# ENCODER.net
KiCad netlist of a schematic drawn in Altium Designer
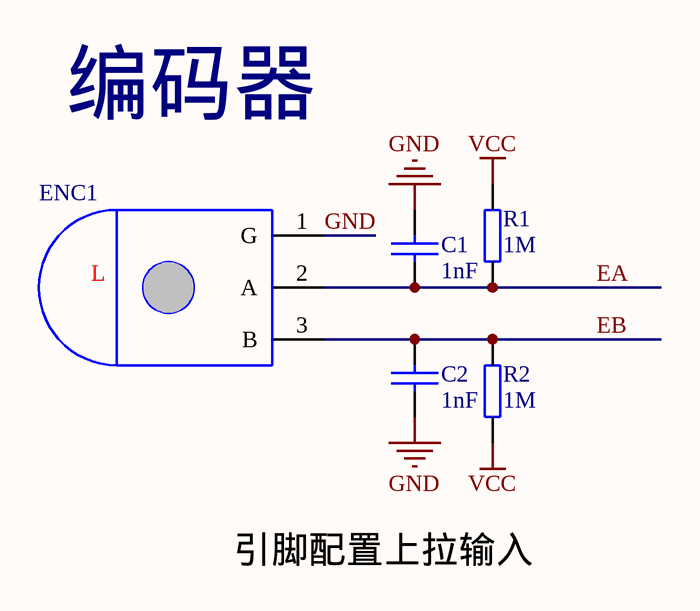
[diagram p0: ENCODER.SchDoc]

(export (version "E")
  (design (tool "Eeschema 10.0.6"))
  (components
    (comp (ref "C1")
      (value "1nF")
      (footprint "0402_C")
      (description "Capacitor")
      (libsource (lib "wch_sch_others(1)") (part "CAP"))
    )
    (comp (ref "C2")
      (value "1nF")
      (footprint "0402_C")
      (description "Capacitor")
      (libsource (lib "wch_sch_others(1)") (part "CAP"))
    )
    (comp (ref "ENC1") (value "~") (footprint "ENC-11-2") (libsource (lib "*") (part "ENC")))
    (comp (ref "R1") (value "1M") (footprint "0402") (libsource (lib "wch_sch_others") (part "RES")))
    (comp (ref "R2") (value "1M") (footprint "0402") (libsource (lib "wch_sch_others") (part "RES")))
  )
  (nets
    (net (code "1") (name "/EA") (class "Default")
      (node (ref "C1") (pin "2") (pinfunction "2_2") (pintype "passive"))
      (node (ref "ENC1") (pin "2") (pinfunction "A_2") (pintype "passive"))
      (node (ref "R1") (pin "2") (pintype "passive"))
    )
    (net (code "2") (name "/EB") (class "Default")
      (node (ref "C2") (pin "2") (pinfunction "2_2") (pintype "passive"))
      (node (ref "ENC1") (pin "3") (pinfunction "B_3") (pintype "passive"))
      (node (ref "R2") (pin "1") (pintype "passive"))
    )
    (net (code "3") (name "GND") (class "Default")
      (node (ref "C1") (pin "1") (pinfunction "1_1") (pintype "passive"))
      (node (ref "C2") (pin "1") (pinfunction "1_1") (pintype "passive"))
      (node (ref "ENC1") (pin "1") (pinfunction "G_1") (pintype "passive"))
    )
    (net (code "4") (name "VCC") (class "Default")
      (node (ref "R1") (pin "1") (pintype "passive"))
      (node (ref "R2") (pin "2") (pintype "passive"))
    )
  )
)
